# FPGA.net
KiCad netlist of a schematic drawn in Altium Designer
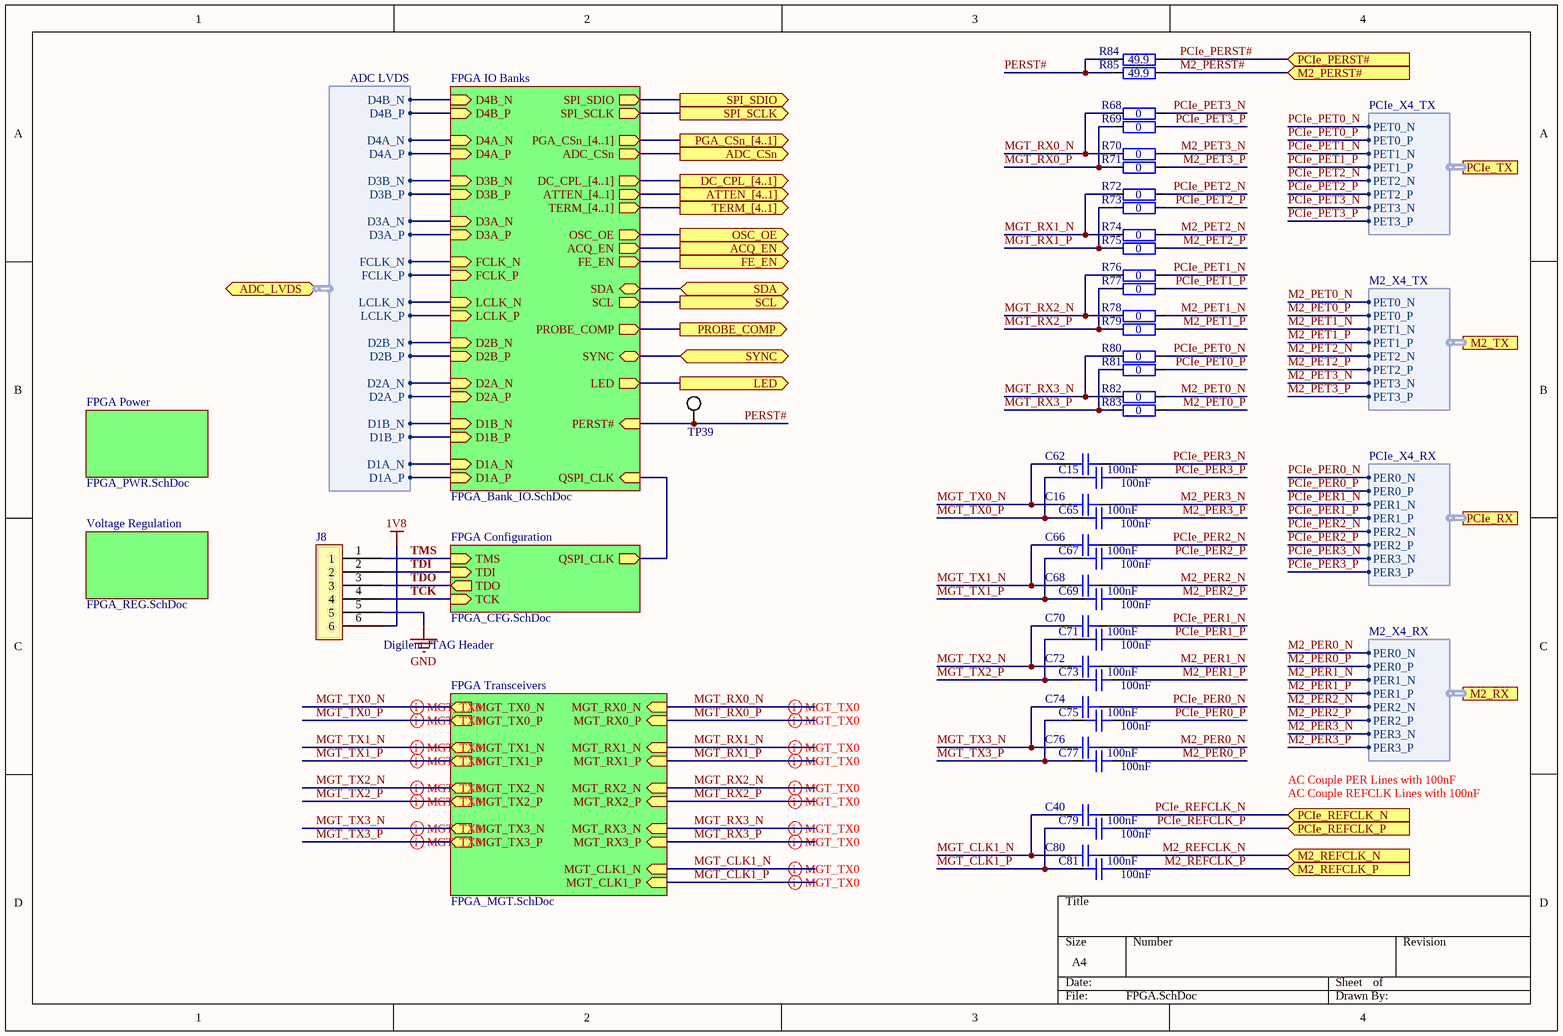
[diagram p0: FPGA.SchDoc]

(export (version "E")
  (design (tool "Eeschema 10.0.6"))
  (components
    (comp (ref "C15")
      (value "100nF")
      (footprint "GEN_C_0201")
      (fields
        (field (name "HOUSE PART NUMBER") "C-100nF-0201-002")
        (field (name "MANUFACTURER") "Murata")
        (field (name "MANUFACTURER PART NUMBER") "GRM033R60J104KE19D")
      )
      (libsource (lib "DSO") (part "CAP 100nF 6.3V X5R 0201"))
    )
    (comp (ref "C16")
      (value "100nF")
      (footprint "GEN_C_0201")
      (fields
        (field (name "HOUSE PART NUMBER") "C-100nF-0201-002")
        (field (name "MANUFACTURER") "Murata")
        (field (name "MANUFACTURER PART NUMBER") "GRM033R60J104KE19D")
      )
      (libsource (lib "DSO") (part "CAP 100nF 6.3V X5R 0201"))
    )
    (comp (ref "C40")
      (value "100nF")
      (footprint "GEN_C_0201")
      (fields
        (field (name "HOUSE PART NUMBER") "C-100nF-0201-002")
        (field (name "MANUFACTURER") "Murata")
        (field (name "MANUFACTURER PART NUMBER") "GRM033R60J104KE19D")
      )
      (libsource (lib "DSO") (part "CAP 100nF 6.3V X5R 0201"))
    )
    (comp (ref "C62")
      (value "100nF")
      (footprint "GEN_C_0201")
      (fields
        (field (name "HOUSE PART NUMBER") "C-100nF-0201-002")
        (field (name "MANUFACTURER") "Murata")
        (field (name "MANUFACTURER PART NUMBER") "GRM033R60J104KE19D")
      )
      (libsource (lib "DSO") (part "CAP 100nF 6.3V X5R 0201"))
    )
    (comp (ref "C65")
      (value "100nF")
      (footprint "GEN_C_0201")
      (fields
        (field (name "HOUSE PART NUMBER") "C-100nF-0201-002")
        (field (name "MANUFACTURER") "Murata")
        (field (name "MANUFACTURER PART NUMBER") "GRM033R60J104KE19D")
      )
      (libsource (lib "DSO") (part "CAP 100nF 6.3V X5R 0201"))
    )
    (comp (ref "C66")
      (value "100nF")
      (footprint "GEN_C_0201")
      (fields
        (field (name "HOUSE PART NUMBER") "C-100nF-0201-002")
        (field (name "MANUFACTURER") "Murata")
        (field (name "MANUFACTURER PART NUMBER") "GRM033R60J104KE19D")
      )
      (libsource (lib "DSO") (part "CAP 100nF 6.3V X5R 0201"))
    )
    (comp (ref "C67")
      (value "100nF")
      (footprint "GEN_C_0201")
      (fields
        (field (name "HOUSE PART NUMBER") "C-100nF-0201-002")
        (field (name "MANUFACTURER") "Murata")
        (field (name "MANUFACTURER PART NUMBER") "GRM033R60J104KE19D")
      )
      (libsource (lib "DSO") (part "CAP 100nF 6.3V X5R 0201"))
    )
    (comp (ref "C68")
      (value "100nF")
      (footprint "GEN_C_0201")
      (fields
        (field (name "HOUSE PART NUMBER") "C-100nF-0201-002")
        (field (name "MANUFACTURER") "Murata")
        (field (name "MANUFACTURER PART NUMBER") "GRM033R60J104KE19D")
      )
      (libsource (lib "DSO") (part "CAP 100nF 6.3V X5R 0201"))
    )
    (comp (ref "C69")
      (value "100nF")
      (footprint "GEN_C_0201")
      (fields
        (field (name "HOUSE PART NUMBER") "C-100nF-0201-002")
        (field (name "MANUFACTURER") "Murata")
        (field (name "MANUFACTURER PART NUMBER") "GRM033R60J104KE19D")
      )
      (libsource (lib "DSO") (part "CAP 100nF 6.3V X5R 0201"))
    )
    (comp (ref "C70")
      (value "100nF")
      (footprint "GEN_C_0201")
      (fields
        (field (name "HOUSE PART NUMBER") "C-100nF-0201-002")
        (field (name "MANUFACTURER") "Murata")
        (field (name "MANUFACTURER PART NUMBER") "GRM033R60J104KE19D")
      )
      (libsource (lib "DSO") (part "CAP 100nF 6.3V X5R 0201"))
    )
    (comp (ref "C71")
      (value "100nF")
      (footprint "GEN_C_0201")
      (fields
        (field (name "HOUSE PART NUMBER") "C-100nF-0201-002")
        (field (name "MANUFACTURER") "Murata")
        (field (name "MANUFACTURER PART NUMBER") "GRM033R60J104KE19D")
      )
      (libsource (lib "DSO") (part "CAP 100nF 6.3V X5R 0201"))
    )
    (comp (ref "C72")
      (value "100nF")
      (footprint "GEN_C_0201")
      (fields
        (field (name "HOUSE PART NUMBER") "C-100nF-0201-002")
        (field (name "MANUFACTURER") "Murata")
        (field (name "MANUFACTURER PART NUMBER") "GRM033R60J104KE19D")
      )
      (libsource (lib "DSO") (part "CAP 100nF 6.3V X5R 0201"))
    )
    (comp (ref "C73")
      (value "100nF")
      (footprint "GEN_C_0201")
      (fields
        (field (name "HOUSE PART NUMBER") "C-100nF-0201-002")
        (field (name "MANUFACTURER") "Murata")
        (field (name "MANUFACTURER PART NUMBER") "GRM033R60J104KE19D")
      )
      (libsource (lib "DSO") (part "CAP 100nF 6.3V X5R 0201"))
    )
    (comp (ref "C74")
      (value "100nF")
      (footprint "GEN_C_0201")
      (fields
        (field (name "HOUSE PART NUMBER") "C-100nF-0201-002")
        (field (name "MANUFACTURER") "Murata")
        (field (name "MANUFACTURER PART NUMBER") "GRM033R60J104KE19D")
      )
      (libsource (lib "DSO") (part "CAP 100nF 6.3V X5R 0201"))
    )
    (comp (ref "C75")
      (value "100nF")
      (footprint "GEN_C_0201")
      (fields
        (field (name "HOUSE PART NUMBER") "C-100nF-0201-002")
        (field (name "MANUFACTURER") "Murata")
        (field (name "MANUFACTURER PART NUMBER") "GRM033R60J104KE19D")
      )
      (libsource (lib "DSO") (part "CAP 100nF 6.3V X5R 0201"))
    )
    (comp (ref "C76")
      (value "100nF")
      (footprint "GEN_C_0201")
      (fields
        (field (name "HOUSE PART NUMBER") "C-100nF-0201-002")
        (field (name "MANUFACTURER") "Murata")
        (field (name "MANUFACTURER PART NUMBER") "GRM033R60J104KE19D")
      )
      (libsource (lib "DSO") (part "CAP 100nF 6.3V X5R 0201"))
    )
    (comp (ref "C77")
      (value "100nF")
      (footprint "GEN_C_0201")
      (fields
        (field (name "HOUSE PART NUMBER") "C-100nF-0201-002")
        (field (name "MANUFACTURER") "Murata")
        (field (name "MANUFACTURER PART NUMBER") "GRM033R60J104KE19D")
      )
      (libsource (lib "DSO") (part "CAP 100nF 6.3V X5R 0201"))
    )
    (comp (ref "C79")
      (value "100nF")
      (footprint "GEN_C_0201")
      (fields
        (field (name "HOUSE PART NUMBER") "C-100nF-0201-002")
        (field (name "MANUFACTURER") "Murata")
        (field (name "MANUFACTURER PART NUMBER") "GRM033R60J104KE19D")
      )
      (libsource (lib "DSO") (part "CAP 100nF 6.3V X5R 0201"))
    )
    (comp (ref "C80")
      (value "100nF")
      (footprint "GEN_C_0201")
      (fields
        (field (name "HOUSE PART NUMBER") "C-100nF-0201-002")
        (field (name "MANUFACTURER") "Murata")
        (field (name "MANUFACTURER PART NUMBER") "GRM033R60J104KE19D")
      )
      (libsource (lib "DSO") (part "CAP 100nF 6.3V X5R 0201"))
    )
    (comp (ref "C81")
      (value "100nF")
      (footprint "GEN_C_0201")
      (fields
        (field (name "HOUSE PART NUMBER") "C-100nF-0201-002")
        (field (name "MANUFACTURER") "Murata")
        (field (name "MANUFACTURER PART NUMBER") "GRM033R60J104KE19D")
      )
      (libsource (lib "DSO") (part "CAP 100nF 6.3V X5R 0201"))
    )
    (comp (ref "J8")
      (value "2.54mm 6 Pin TH")
      (footprint "GEN_2.54mm_6_Pin_TH_RA")
      (fields
        (field (name "MANUFACTURER") "Wurth Electronics")
        (field (name "MANUFACTURER PART NUMBER") "61300611021")
      )
      (libsource (lib "DSO") (part "CONN 2.54mm 6 Pin TH RA"))
    )
    (comp (ref "R68")
      (value "0")
      (footprint "GEN_R_0201")
      (fields
        (field (name "TOLERANCE") "1%")
        (field (name "MANUFACTURER") "Stackpole Electronics")
        (field (name "MANUFACTURER PART NUMBER") "RMCF0201ZT0R00")
      )
      (libsource (lib "DSO") (part "RES 0 OHM 1% 1/20W 0201"))
    )
    (comp (ref "R69")
      (value "0")
      (footprint "GEN_R_0201")
      (fields
        (field (name "TOLERANCE") "1%")
        (field (name "MANUFACTURER") "Stackpole Electronics")
        (field (name "MANUFACTURER PART NUMBER") "RMCF0201ZT0R00")
      )
      (libsource (lib "DSO") (part "RES 0 OHM 1% 1/20W 0201"))
    )
    (comp (ref "R70")
      (value "0")
      (footprint "GEN_R_0201")
      (fields
        (field (name "TOLERANCE") "1%")
        (field (name "MANUFACTURER") "Stackpole Electronics")
        (field (name "MANUFACTURER PART NUMBER") "RMCF0201ZT0R00")
      )
      (libsource (lib "DSO") (part "RES 0 OHM 1% 1/20W 0201"))
    )
    (comp (ref "R71")
      (value "0")
      (footprint "GEN_R_0201")
      (fields
        (field (name "TOLERANCE") "1%")
        (field (name "MANUFACTURER") "Stackpole Electronics")
        (field (name "MANUFACTURER PART NUMBER") "RMCF0201ZT0R00")
      )
      (libsource (lib "DSO") (part "RES 0 OHM 1% 1/20W 0201"))
    )
    (comp (ref "R72")
      (value "0")
      (footprint "GEN_R_0201")
      (fields
        (field (name "TOLERANCE") "1%")
        (field (name "MANUFACTURER") "Stackpole Electronics")
        (field (name "MANUFACTURER PART NUMBER") "RMCF0201ZT0R00")
      )
      (libsource (lib "DSO") (part "RES 0 OHM 1% 1/20W 0201"))
    )
    (comp (ref "R73")
      (value "0")
      (footprint "GEN_R_0201")
      (fields
        (field (name "TOLERANCE") "1%")
        (field (name "MANUFACTURER") "Stackpole Electronics")
        (field (name "MANUFACTURER PART NUMBER") "RMCF0201ZT0R00")
      )
      (libsource (lib "DSO") (part "RES 0 OHM 1% 1/20W 0201"))
    )
    (comp (ref "R74")
      (value "0")
      (footprint "GEN_R_0201")
      (fields
        (field (name "TOLERANCE") "1%")
        (field (name "MANUFACTURER") "Stackpole Electronics")
        (field (name "MANUFACTURER PART NUMBER") "RMCF0201ZT0R00")
      )
      (libsource (lib "DSO") (part "RES 0 OHM 1% 1/20W 0201"))
    )
    (comp (ref "R75")
      (value "0")
      (footprint "GEN_R_0201")
      (fields
        (field (name "TOLERANCE") "1%")
        (field (name "MANUFACTURER") "Stackpole Electronics")
        (field (name "MANUFACTURER PART NUMBER") "RMCF0201ZT0R00")
      )
      (libsource (lib "DSO") (part "RES 0 OHM 1% 1/20W 0201"))
    )
    (comp (ref "R76")
      (value "0")
      (footprint "GEN_R_0201")
      (fields
        (field (name "TOLERANCE") "1%")
        (field (name "MANUFACTURER") "Stackpole Electronics")
        (field (name "MANUFACTURER PART NUMBER") "RMCF0201ZT0R00")
      )
      (libsource (lib "DSO") (part "RES 0 OHM 1% 1/20W 0201"))
    )
    (comp (ref "R77")
      (value "0")
      (footprint "GEN_R_0201")
      (fields
        (field (name "TOLERANCE") "1%")
        (field (name "MANUFACTURER") "Stackpole Electronics")
        (field (name "MANUFACTURER PART NUMBER") "RMCF0201ZT0R00")
      )
      (libsource (lib "DSO") (part "RES 0 OHM 1% 1/20W 0201"))
    )
    (comp (ref "R78")
      (value "0")
      (footprint "GEN_R_0201")
      (fields
        (field (name "TOLERANCE") "1%")
        (field (name "MANUFACTURER") "Stackpole Electronics")
        (field (name "MANUFACTURER PART NUMBER") "RMCF0201ZT0R00")
      )
      (libsource (lib "DSO") (part "RES 0 OHM 1% 1/20W 0201"))
    )
    (comp (ref "R79")
      (value "0")
      (footprint "GEN_R_0201")
      (fields
        (field (name "TOLERANCE") "1%")
        (field (name "MANUFACTURER") "Stackpole Electronics")
        (field (name "MANUFACTURER PART NUMBER") "RMCF0201ZT0R00")
      )
      (libsource (lib "DSO") (part "RES 0 OHM 1% 1/20W 0201"))
    )
    (comp (ref "R80")
      (value "0")
      (footprint "GEN_R_0201")
      (fields
        (field (name "TOLERANCE") "1%")
        (field (name "MANUFACTURER") "Stackpole Electronics")
        (field (name "MANUFACTURER PART NUMBER") "RMCF0201ZT0R00")
      )
      (libsource (lib "DSO") (part "RES 0 OHM 1% 1/20W 0201"))
    )
    (comp (ref "R81")
      (value "0")
      (footprint "GEN_R_0201")
      (fields
        (field (name "TOLERANCE") "1%")
        (field (name "MANUFACTURER") "Stackpole Electronics")
        (field (name "MANUFACTURER PART NUMBER") "RMCF0201ZT0R00")
      )
      (libsource (lib "DSO") (part "RES 0 OHM 1% 1/20W 0201"))
    )
    (comp (ref "R82")
      (value "0")
      (footprint "GEN_R_0201")
      (fields
        (field (name "TOLERANCE") "1%")
        (field (name "MANUFACTURER") "Stackpole Electronics")
        (field (name "MANUFACTURER PART NUMBER") "RMCF0201ZT0R00")
      )
      (libsource (lib "DSO") (part "RES 0 OHM 1% 1/20W 0201"))
    )
    (comp (ref "R83")
      (value "0")
      (footprint "GEN_R_0201")
      (fields
        (field (name "TOLERANCE") "1%")
        (field (name "MANUFACTURER") "Stackpole Electronics")
        (field (name "MANUFACTURER PART NUMBER") "RMCF0201ZT0R00")
      )
      (libsource (lib "DSO") (part "RES 0 OHM 1% 1/20W 0201"))
    )
    (comp (ref "R84")
      (value "49.9")
      (footprint "GEN_R_0402")
      (fields
        (field (name "TOLERANCE") "1%")
        (field (name "MANUFACTURER") "Yageo")
        (field (name "MANUFACTURER PART NUMBER") "RC0402FR-0749R9L")
      )
      (libsource (lib "DSO") (part "RES 49.9 OHM 1% 1/10W 0402"))
    )
    (comp (ref "R85")
      (value "49.9")
      (footprint "GEN_R_0402")
      (fields
        (field (name "TOLERANCE") "1%")
        (field (name "MANUFACTURER") "Yageo")
        (field (name "MANUFACTURER PART NUMBER") "RC0402FR-0749R9L")
      )
      (libsource (lib "DSO") (part "RES 49.9 OHM 1% 1/10W 0402"))
    )
    (comp (ref "TP39") (value "PCB") (footprint "GEN_TP_PCB") (libsource (lib "DSO") (part "TP PCB 1mm")))
  )
  (nets
    (net (code "49") (name "/M2_PER0_N") (class "Default")
      (node (ref "C76") (pin "1") (pinfunction "1_1") (pintype "passive"))
    )
    (net (code "50") (name "/M2_PER0_P") (class "Default")
      (node (ref "C77") (pin "1") (pinfunction "1_1") (pintype "passive"))
    )
    (net (code "51") (name "/M2_PER1_N") (class "Default")
      (node (ref "C72") (pin "1") (pinfunction "1_1") (pintype "passive"))
    )
    (net (code "52") (name "/M2_PER1_P") (class "Default")
      (node (ref "C73") (pin "1") (pinfunction "1_1") (pintype "passive"))
    )
    (net (code "53") (name "/M2_PER2_N") (class "Default")
      (node (ref "C68") (pin "1") (pinfunction "1_1") (pintype "passive"))
    )
    (net (code "54") (name "/M2_PER2_P") (class "Default")
      (node (ref "C69") (pin "1") (pinfunction "1_1") (pintype "passive"))
    )
    (net (code "55") (name "/M2_PER3_N") (class "Default")
      (node (ref "C16") (pin "1") (pinfunction "1_1") (pintype "passive"))
    )
    (net (code "56") (name "/M2_PER3_P") (class "Default")
      (node (ref "C65") (pin "1") (pinfunction "1_1") (pintype "passive"))
    )
    (net (code "57") (name "/M2_PERST#") (class "Default")
      (node (ref "R85") (pin "2") (pinfunction "2_2") (pintype "passive"))
    )
    (net (code "58") (name "/M2_PET0_N") (class "Default")
      (node (ref "R82") (pin "2") (pinfunction "2_2") (pintype "passive"))
    )
    (net (code "59") (name "/M2_PET0_P") (class "Default")
      (node (ref "R83") (pin "2") (pinfunction "2_2") (pintype "passive"))
    )
    (net (code "60") (name "/M2_PET1_N") (class "Default")
      (node (ref "R78") (pin "2") (pinfunction "2_2") (pintype "passive"))
    )
    (net (code "61") (name "/M2_PET1_P") (class "Default")
      (node (ref "R79") (pin "2") (pinfunction "2_2") (pintype "passive"))
    )
    (net (code "62") (name "/M2_PET2_N") (class "Default")
      (node (ref "R74") (pin "2") (pinfunction "2_2") (pintype "passive"))
    )
    (net (code "63") (name "/M2_PET2_P") (class "Default")
      (node (ref "R75") (pin "2") (pinfunction "2_2") (pintype "passive"))
    )
    (net (code "64") (name "/M2_PET3_N") (class "Default")
      (node (ref "R70") (pin "2") (pinfunction "2_2") (pintype "passive"))
    )
    (net (code "65") (name "/M2_PET3_P") (class "Default")
      (node (ref "R71") (pin "2") (pinfunction "2_2") (pintype "passive"))
    )
    (net (code "66") (name "/M2_REFCLK_N") (class "Default")
      (node (ref "C80") (pin "1") (pinfunction "1_1") (pintype "passive"))
    )
    (net (code "67") (name "/M2_REFCLK_P") (class "Default")
      (node (ref "C81") (pin "1") (pinfunction "1_1") (pintype "passive"))
    )
    (net (code "68") (name "/MGT_CLK1_N") (class "Default")
      (node (ref "C40") (pin "2") (pinfunction "2_2") (pintype "passive"))
      (node (ref "C80") (pin "2") (pinfunction "2_2") (pintype "passive"))
    )
    (net (code "69") (name "/MGT_CLK1_P") (class "Default")
      (node (ref "C79") (pin "2") (pinfunction "2_2") (pintype "passive"))
      (node (ref "C81") (pin "2") (pinfunction "2_2") (pintype "passive"))
    )
    (net (code "70") (name "/MGT_RX0_N") (class "Default")
      (node (ref "R68") (pin "1") (pinfunction "1_1") (pintype "passive"))
      (node (ref "R70") (pin "1") (pinfunction "1_1") (pintype "passive"))
    )
    (net (code "71") (name "/MGT_RX0_P") (class "Default")
      (node (ref "R69") (pin "1") (pinfunction "1_1") (pintype "passive"))
      (node (ref "R71") (pin "1") (pinfunction "1_1") (pintype "passive"))
    )
    (net (code "72") (name "/MGT_RX1_N") (class "Default")
      (node (ref "R72") (pin "1") (pinfunction "1_1") (pintype "passive"))
      (node (ref "R74") (pin "1") (pinfunction "1_1") (pintype "passive"))
    )
    (net (code "73") (name "/MGT_RX1_P") (class "Default")
      (node (ref "R73") (pin "1") (pinfunction "1_1") (pintype "passive"))
      (node (ref "R75") (pin "1") (pinfunction "1_1") (pintype "passive"))
    )
    (net (code "74") (name "/MGT_RX2_N") (class "Default")
      (node (ref "R76") (pin "1") (pinfunction "1_1") (pintype "passive"))
      (node (ref "R78") (pin "1") (pinfunction "1_1") (pintype "passive"))
    )
    (net (code "75") (name "/MGT_RX2_P") (class "Default")
      (node (ref "R77") (pin "1") (pinfunction "1_1") (pintype "passive"))
      (node (ref "R79") (pin "1") (pinfunction "1_1") (pintype "passive"))
    )
    (net (code "76") (name "/MGT_RX3_N") (class "Default")
      (node (ref "R80") (pin "1") (pinfunction "1_1") (pintype "passive"))
      (node (ref "R82") (pin "1") (pinfunction "1_1") (pintype "passive"))
    )
    (net (code "77") (name "/MGT_RX3_P") (class "Default")
      (node (ref "R81") (pin "1") (pinfunction "1_1") (pintype "passive"))
      (node (ref "R83") (pin "1") (pinfunction "1_1") (pintype "passive"))
    )
    (net (code "78") (name "/MGT_TX0_N") (class "Default")
      (node (ref "C16") (pin "2") (pinfunction "2_2") (pintype "passive"))
      (node (ref "C62") (pin "2") (pinfunction "2_2") (pintype "passive"))
    )
    (net (code "79") (name "/MGT_TX0_P") (class "Default")
      (node (ref "C15") (pin "2") (pinfunction "2_2") (pintype "passive"))
      (node (ref "C65") (pin "2") (pinfunction "2_2") (pintype "passive"))
    )
    (net (code "80") (name "/MGT_TX1_N") (class "Default")
      (node (ref "C66") (pin "2") (pinfunction "2_2") (pintype "passive"))
      (node (ref "C68") (pin "2") (pinfunction "2_2") (pintype "passive"))
    )
    (net (code "81") (name "/MGT_TX1_P") (class "Default")
      (node (ref "C67") (pin "2") (pinfunction "2_2") (pintype "passive"))
      (node (ref "C69") (pin "2") (pinfunction "2_2") (pintype "passive"))
    )
    (net (code "82") (name "/MGT_TX2_N") (class "Default")
      (node (ref "C70") (pin "2") (pinfunction "2_2") (pintype "passive"))
      (node (ref "C72") (pin "2") (pinfunction "2_2") (pintype "passive"))
    )
    (net (code "83") (name "/MGT_TX2_P") (class "Default")
      (node (ref "C71") (pin "2") (pinfunction "2_2") (pintype "passive"))
      (node (ref "C73") (pin "2") (pinfunction "2_2") (pintype "passive"))
    )
    (net (code "84") (name "/MGT_TX3_N") (class "Default")
      (node (ref "C74") (pin "2") (pinfunction "2_2") (pintype "passive"))
      (node (ref "C76") (pin "2") (pinfunction "2_2") (pintype "passive"))
    )
    (net (code "85") (name "/MGT_TX3_P") (class "Default")
      (node (ref "C75") (pin "2") (pinfunction "2_2") (pintype "passive"))
      (node (ref "C77") (pin "2") (pinfunction "2_2") (pintype "passive"))
    )
    (net (code "87") (name "/PCIe_PER0_N") (class "Default")
      (node (ref "C74") (pin "1") (pinfunction "1_1") (pintype "passive"))
    )
    (net (code "88") (name "/PCIe_PER0_P") (class "Default")
      (node (ref "C75") (pin "1") (pinfunction "1_1") (pintype "passive"))
    )
    (net (code "89") (name "/PCIe_PER1_N") (class "Default")
      (node (ref "C70") (pin "1") (pinfunction "1_1") (pintype "passive"))
    )
    (net (code "90") (name "/PCIe_PER1_P") (class "Default")
      (node (ref "C71") (pin "1") (pinfunction "1_1") (pintype "passive"))
    )
    (net (code "91") (name "/PCIe_PER2_N") (class "Default")
      (node (ref "C66") (pin "1") (pinfunction "1_1") (pintype "passive"))
    )
    (net (code "92") (name "/PCIe_PER2_P") (class "Default")
      (node (ref "C67") (pin "1") (pinfunction "1_1") (pintype "passive"))
    )
    (net (code "93") (name "/PCIe_PER3_N") (class "Default")
      (node (ref "C62") (pin "1") (pinfunction "1_1") (pintype "passive"))
    )
    (net (code "94") (name "/PCIe_PER3_P") (class "Default")
      (node (ref "C15") (pin "1") (pinfunction "1_1") (pintype "passive"))
    )
    (net (code "95") (name "/PCIe_PERST#") (class "Default")
      (node (ref "R84") (pin "2") (pinfunction "2_2") (pintype "passive"))
    )
    (net (code "96") (name "/PCIe_PET0_N") (class "Default")
      (node (ref "R80") (pin "2") (pinfunction "2_2") (pintype "passive"))
    )
    (net (code "97") (name "/PCIe_PET0_P") (class "Default")
      (node (ref "R81") (pin "2") (pinfunction "2_2") (pintype "passive"))
    )
    (net (code "98") (name "/PCIe_PET1_N") (class "Default")
      (node (ref "R76") (pin "2") (pinfunction "2_2") (pintype "passive"))
    )
    (net (code "99") (name "/PCIe_PET1_P") (class "Default")
      (node (ref "R77") (pin "2") (pinfunction "2_2") (pintype "passive"))
    )
    (net (code "100") (name "/PCIe_PET2_N") (class "Default")
      (node (ref "R72") (pin "2") (pinfunction "2_2") (pintype "passive"))
    )
    (net (code "101") (name "/PCIe_PET2_P") (class "Default")
      (node (ref "R73") (pin "2") (pinfunction "2_2") (pintype "passive"))
    )
    (net (code "102") (name "/PCIe_PET3_N") (class "Default")
      (node (ref "R68") (pin "2") (pinfunction "2_2") (pintype "passive"))
    )
    (net (code "103") (name "/PCIe_PET3_P") (class "Default")
      (node (ref "R69") (pin "2") (pinfunction "2_2") (pintype "passive"))
    )
    (net (code "104") (name "/PCIe_REFCLK_N") (class "Default")
      (node (ref "C40") (pin "1") (pinfunction "1_1") (pintype "passive"))
    )
    (net (code "105") (name "/PCIe_REFCLK_P") (class "Default")
      (node (ref "C79") (pin "1") (pinfunction "1_1") (pintype "passive"))
    )
    (net (code "106") (name "/PERST#") (class "Default")
      (node (ref "R84") (pin "1") (pinfunction "1_1") (pintype "passive"))
      (node (ref "R85") (pin "1") (pinfunction "1_1") (pintype "passive"))
      (node (ref "TP39") (pin "1") (pinfunction "1_1") (pintype "passive"))
    )
    (net (code "115") (name "/TCK") (class "Default")
      (node (ref "J8") (pin "4") (pinfunction "4_4") (pintype "passive"))
    )
    (net (code "116") (name "/TDI") (class "Default")
      (node (ref "J8") (pin "2") (pinfunction "2_2") (pintype "passive"))
    )
    (net (code "117") (name "/TDO") (class "Default")
      (node (ref "J8") (pin "3") (pinfunction "3_3") (pintype "passive"))
    )
    (net (code "119") (name "/TMS") (class "Default")
      (node (ref "J8") (pin "1") (pinfunction "1_1") (pintype "passive"))
    )
    (net (code "125") (name "1V8") (class "Default")
      (node (ref "J8") (pin "6") (pinfunction "6_6") (pintype "passive"))
    )
    (net (code "126") (name "GND") (class "Default")
      (node (ref "J8") (pin "5") (pinfunction "5_5") (pintype "passive"))
    )
  )
)
